# Photodiode.net
KiCad netlist of a schematic drawn in Altium Designer
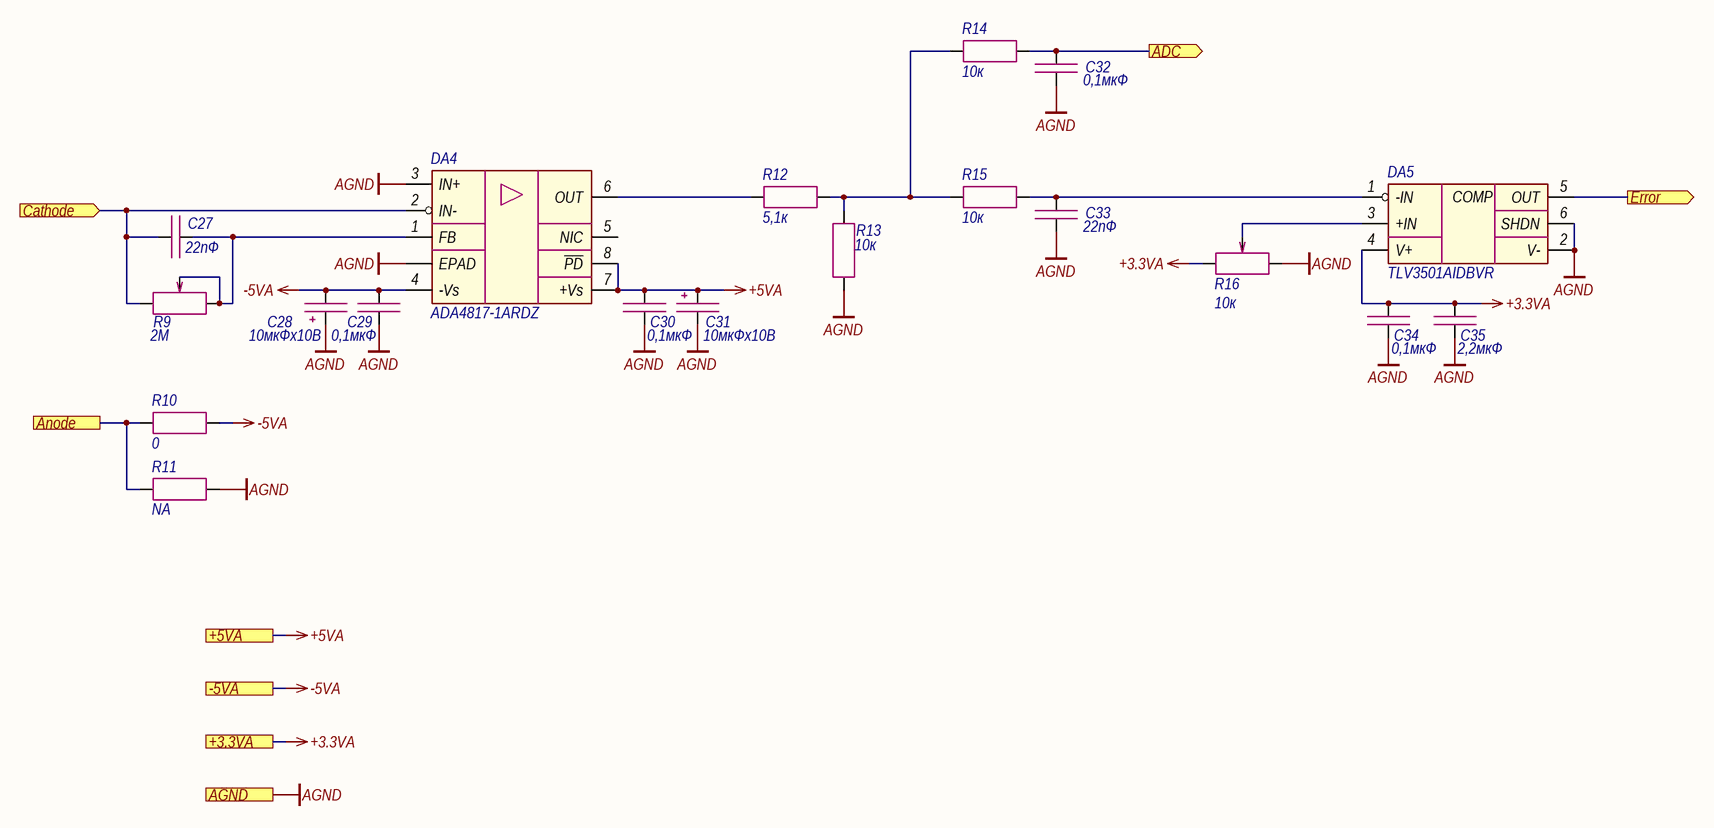
[diagram p0: Photodiode.SchDoc]

(export (version "E")
  (design (tool "Eeschema 10.0.6"))
  (components
    (comp (ref "C27")
      (value "22пФ")
      (footprint "Pcb_library:CAP_0603")
      (fields (field (name "MANUFACTURER") "Murata"))
      (libsource (lib "Schem_library") (part "Capacitor"))
    )
    (comp (ref "C28")
      (value "10мкФх10B")
      (footprint "Pcb_library:CAP_A")
      (libsource (lib "Schem_library") (part "Capacitor_Polar"))
    )
    (comp (ref "C29")
      (value "0,1мкФ")
      (footprint "Pcb_library:CAP_0603")
      (fields (field (name "MANUFACTURER") "Murata"))
      (libsource (lib "Schem_library") (part "Capacitor"))
    )
    (comp (ref "C30")
      (value "0,1мкФ")
      (footprint "Pcb_library:CAP_0603")
      (fields (field (name "MANUFACTURER") "Murata"))
      (libsource (lib "Schem_library") (part "Capacitor"))
    )
    (comp (ref "C31")
      (value "10мкФх10B")
      (footprint "Pcb_library:CAP_A")
      (libsource (lib "Schem_library") (part "Capacitor_Polar"))
    )
    (comp (ref "C32")
      (value "0,1мкФ")
      (footprint "Pcb_library:CAP_0603")
      (fields (field (name "MANUFACTURER") "Murata"))
      (libsource (lib "Schem_library") (part "Capacitor"))
    )
    (comp (ref "C33")
      (value "22пФ")
      (footprint "Pcb_library:CAP_0603")
      (fields (field (name "MANUFACTURER") "Murata"))
      (libsource (lib "Schem_library") (part "Capacitor"))
    )
    (comp (ref "C34")
      (value "0,1мкФ")
      (footprint "Pcb_library:CAP_0603")
      (fields (field (name "MANUFACTURER") "Murata"))
      (libsource (lib "Schem_library") (part "Capacitor"))
    )
    (comp (ref "C35")
      (value "2,2мкФ")
      (footprint "Pcb_library:CAP_0603")
      (fields (field (name "MANUFACTURER") "Murata"))
      (libsource (lib "Schem_library") (part "Capacitor"))
    )
    (comp (ref "DA4")
      (value "ADA4817-1ARDZ")
      (footprint "Pcb_library:SOIC-8 EPAD")
      (fields (field (name "MANUFACTURER") "Analog Devices"))
      (libsource (lib "Schem_library") (part "ADA4817-1ARDZ"))
    )
    (comp (ref "DA5")
      (value "TLV3501AIDBVR")
      (footprint "Pcb_library:SOT-23-6")
      (fields (field (name "MANUFACTURER") "Texas Instruments"))
      (libsource (lib "Schem_library") (part "TLV3501"))
    )
    (comp (ref "R9")
      (value "2М")
      (footprint "Pcb_library:3224W")
      (fields (field (name "MANUFACTURER") "Bourns"))
      (libsource (lib "Schem_library") (part "Resistor_Variable"))
    )
    (comp (ref "R10")
      (value "0")
      (footprint "Pcb_library:RES_0603")
      (fields (field (name "MANUFACTURER") "Yageo"))
      (libsource (lib "Schem_library") (part "Resistor"))
    )
    (comp (ref "R11")
      (value "NA")
      (footprint "Pcb_library:RES_0603")
      (libsource (lib "Schem_library") (part "Resistor"))
    )
    (comp (ref "R12")
      (value "5,1к")
      (footprint "Pcb_library:RES_0603")
      (fields (field (name "MANUFACTURER") "Yageo"))
      (libsource (lib "Schem_library") (part "Resistor"))
    )
    (comp (ref "R13")
      (value "10к")
      (footprint "Pcb_library:RES_0603")
      (fields (field (name "MANUFACTURER") "Yageo"))
      (libsource (lib "Schem_library") (part "Resistor"))
    )
    (comp (ref "R14")
      (value "10к")
      (footprint "Pcb_library:RES_0603")
      (fields (field (name "MANUFACTURER") "Yageo"))
      (libsource (lib "Schem_library") (part "Resistor"))
    )
    (comp (ref "R15")
      (value "10к")
      (footprint "Pcb_library:RES_0603")
      (fields (field (name "MANUFACTURER") "Yageo"))
      (libsource (lib "Schem_library") (part "Resistor"))
    )
    (comp (ref "R16")
      (value "10к")
      (footprint "Pcb_library:3224W")
      (fields (field (name "MANUFACTURER") "Bourns"))
      (libsource (lib "Schem_library") (part "Resistor_Variable"))
    )
  )
  (nets
    (net (code "1") (name "+3.3VA") (class "Default")
      (node (ref "C34") (pin "1") (pinfunction "1_1") (pintype "passive"))
      (node (ref "C35") (pin "1") (pinfunction "1_1") (pintype "passive"))
      (node (ref "DA5") (pin "4") (pinfunction "V+_4") (pintype "passive"))
      (node (ref "R16") (pin "3") (pintype "passive"))
    )
    (net (code "2") (name "+5VA") (class "Default")
      (node (ref "C30") (pin "1") (pinfunction "1_1") (pintype "passive"))
      (node (ref "C31") (pin "1") (pinfunction "1_1") (pintype "passive"))
      (node (ref "DA4") (pin "7") (pinfunction "+Vs_7") (pintype "passive"))
      (node (ref "DA4") (pin "8") (pinfunction "~{PD}_8") (pintype "passive"))
    )
    (net (code "3") (name "-5VA") (class "Default")
      (node (ref "C28") (pin "2") (pinfunction "2_2") (pintype "passive"))
      (node (ref "C29") (pin "1") (pinfunction "1_1") (pintype "passive"))
      (node (ref "DA4") (pin "4") (pinfunction "-Vs_4") (pintype "passive"))
      (node (ref "R10") (pin "1") (pinfunction "1_1") (pintype "passive"))
    )
    (net (code "4") (name "/ADC") (class "Default")
      (node (ref "C32") (pin "1") (pinfunction "1_1") (pintype "passive"))
      (node (ref "R14") (pin "2") (pinfunction "2_2") (pintype "passive"))
    )
    (net (code "5") (name "/Anode") (class "Default")
      (node (ref "R10") (pin "2") (pinfunction "2_2") (pintype "passive"))
      (node (ref "R11") (pin "1") (pinfunction "1_1") (pintype "passive"))
    )
    (net (code "6") (name "/Cathode") (class "Default")
      (node (ref "C27") (pin "2") (pinfunction "2_2") (pintype "passive"))
      (node (ref "DA4") (pin "2") (pinfunction "IN-_2") (pintype "passive"))
      (node (ref "R9") (pin "1") (pintype "passive"))
    )
    (net (code "7") (name "/Error") (class "Default")
      (node (ref "DA5") (pin "5") (pinfunction "OUT_5") (pintype "passive"))
    )
    (net (code "8") (name "AGND") (class "Default")
      (node (ref "C28") (pin "1") (pinfunction "1_1") (pintype "passive"))
      (node (ref "C29") (pin "2") (pinfunction "2_2") (pintype "passive"))
      (node (ref "C30") (pin "2") (pinfunction "2_2") (pintype "passive"))
      (node (ref "C31") (pin "2") (pinfunction "2_2") (pintype "passive"))
      (node (ref "C32") (pin "2") (pinfunction "2_2") (pintype "passive"))
      (node (ref "C33") (pin "2") (pinfunction "2_2") (pintype "passive"))
      (node (ref "C34") (pin "2") (pinfunction "2_2") (pintype "passive"))
      (node (ref "C35") (pin "2") (pinfunction "2_2") (pintype "passive"))
      (node (ref "DA4") (pin "3") (pinfunction "IN+_3") (pintype "passive"))
      (node (ref "DA4") (pin "EPAD") (pinfunction "EPAD_EPAD") (pintype "passive"))
      (node (ref "DA5") (pin "2") (pinfunction "V-_2") (pintype "passive"))
      (node (ref "DA5") (pin "6") (pinfunction "SHDN_6") (pintype "passive"))
      (node (ref "R11") (pin "2") (pinfunction "2_2") (pintype "passive"))
      (node (ref "R13") (pin "2") (pinfunction "2_2") (pintype "passive"))
      (node (ref "R16") (pin "1") (pintype "passive"))
    )
    (net (code "9") (name "Net-(DA4-FB)") (class "Default")
      (node (ref "C27") (pin "1") (pinfunction "1_1") (pintype "passive"))
      (node (ref "DA4") (pin "1") (pinfunction "FB_1") (pintype "passive"))
      (node (ref "R9") (pin "2") (pintype "passive"))
      (node (ref "R9") (pin "3") (pintype "passive"))
    )
    (net (code "10") (name "Net-(DA4-OUT)") (class "Default")
      (node (ref "DA4") (pin "6") (pinfunction "OUT_6") (pintype "passive"))
      (node (ref "R12") (pin "1") (pinfunction "1_1") (pintype "passive"))
    )
    (net (code "11") (name "Net-(DA5-+IN)") (class "Default")
      (node (ref "DA5") (pin "3") (pinfunction "+IN_3") (pintype "passive"))
      (node (ref "R16") (pin "2") (pintype "passive"))
    )
    (net (code "12") (name "Net-(DA5--IN)") (class "Default")
      (node (ref "C33") (pin "1") (pinfunction "1_1") (pintype "passive"))
      (node (ref "DA5") (pin "1") (pinfunction "-IN_1") (pintype "passive"))
      (node (ref "R15") (pin "2") (pinfunction "2_2") (pintype "passive"))
    )
    (net (code "13") (name "Net-(R12-Pad2)") (class "Default")
      (node (ref "R12") (pin "2") (pinfunction "2_2") (pintype "passive"))
      (node (ref "R13") (pin "1") (pinfunction "1_1") (pintype "passive"))
      (node (ref "R14") (pin "1") (pinfunction "1_1") (pintype "passive"))
      (node (ref "R15") (pin "1") (pinfunction "1_1") (pintype "passive"))
    )
    (net (code "14") (name "unconnected-(DA4-NIC-Pad5)") (class "Default")
      (node (ref "DA4") (pin "5") (pinfunction "NIC_5") (pintype "passive"))
    )
  )
)
